# untitled.net
KiCad netlist of a schematic drawn in EAGLE
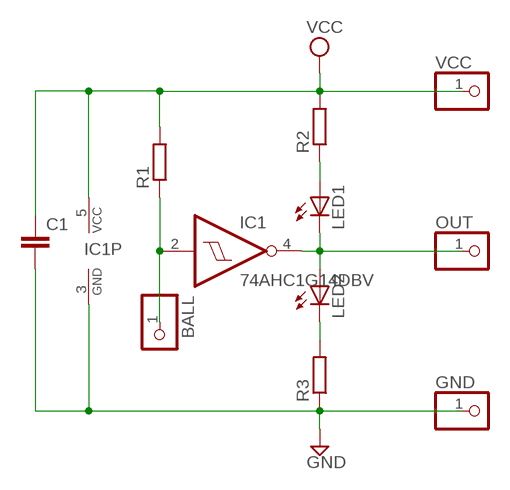
[diagram p0: schematic, sheet 1]

(export (version "E")
  (design (tool "Eeschema 10.0.6"))
  (components
    (comp (ref "BALL")
      (value "PINHD-1X1")
      (footprint "eagle-import:1X01")
      (libsource (lib "eagle-import") (part "PINHD-1X1"))
    )
    (comp (ref "C1")
      (value "C-EUC0805")
      (footprint "eagle-import:C0805")
      (libsource (lib "eagle-import") (part "C-EUC0805"))
    )
    (comp (ref "GND")
      (value "PINHD-1X1")
      (footprint "eagle-import:1X01")
      (libsource (lib "eagle-import") (part "PINHD-1X1"))
    )
    (comp (ref "IC1")
      (value "74AHC1G14DBV")
      (footprint "eagle-import:SOT23-5")
      (libsource (lib "eagle-import") (part "741G14DBVAHC"))
    )
    (comp (ref "LED1")
      (value "LEDCHIP-LED0805")
      (footprint "eagle-import:CHIP-LED0805")
      (libsource (lib "eagle-import") (part "LEDCHIP-LED0805"))
    )
    (comp (ref "LED2")
      (value "LEDCHIP-LED0805")
      (footprint "eagle-import:CHIP-LED0805")
      (libsource (lib "eagle-import") (part "LEDCHIP-LED0805"))
    )
    (comp (ref "OUT")
      (value "PINHD-1X1")
      (footprint "eagle-import:1X01")
      (libsource (lib "eagle-import") (part "PINHD-1X1"))
    )
    (comp (ref "R1")
      (value "R-EU_R0805")
      (footprint "eagle-import:R0805")
      (libsource (lib "eagle-import") (part "R-EU_R0805"))
    )
    (comp (ref "R2")
      (value "R-EU_R0805")
      (footprint "eagle-import:R0805")
      (libsource (lib "eagle-import") (part "R-EU_R0805"))
    )
    (comp (ref "R3")
      (value "R-EU_R0805")
      (footprint "eagle-import:R0805")
      (libsource (lib "eagle-import") (part "R-EU_R0805"))
    )
    (comp (ref "VCC")
      (value "PINHD-1X1")
      (footprint "eagle-import:1X01")
      (libsource (lib "eagle-import") (part "PINHD-1X1"))
    )
  )
  (nets
    (net (code "1") (name "GND") (class "Default")
      (node (ref "C1") (pin "2") (pinfunction "2_2") (pintype "passive"))
      (node (ref "GND") (pin "1") (pinfunction "1_1") (pintype "passive"))
      (node (ref "IC1") (pin "3") (pinfunction "GND_3") (pintype "power_in"))
      (node (ref "R3") (pin "1") (pinfunction "1_1") (pintype "passive"))
    )
    (net (code "2") (name "Net-(IC1A-I)") (class "Default")
      (node (ref "BALL") (pin "1") (pinfunction "1_1") (pintype "passive"))
      (node (ref "IC1") (pin "2") (pinfunction "I_2") (pintype "input"))
      (node (ref "R1") (pin "1") (pinfunction "1_1") (pintype "passive"))
    )
    (net (code "3") (name "Net-(IC1A-O)") (class "Default")
      (node (ref "IC1") (pin "4") (pinfunction "O_4") (pintype "output"))
      (node (ref "LED1") (pin "C") (pinfunction "C_C") (pintype "passive"))
      (node (ref "LED2") (pin "A") (pinfunction "A_A") (pintype "passive"))
      (node (ref "OUT") (pin "1") (pinfunction "1_1") (pintype "passive"))
    )
    (net (code "4") (name "Net-(LED1-PadA)") (class "Default")
      (node (ref "LED1") (pin "A") (pinfunction "A_A") (pintype "passive"))
      (node (ref "R2") (pin "1") (pinfunction "1_1") (pintype "passive"))
    )
    (net (code "5") (name "Net-(LED2-PadC)") (class "Default")
      (node (ref "LED2") (pin "C") (pinfunction "C_C") (pintype "passive"))
      (node (ref "R3") (pin "2") (pinfunction "2_2") (pintype "passive"))
    )
    (net (code "6") (name "VCC") (class "Default")
      (node (ref "C1") (pin "1") (pinfunction "1_1") (pintype "passive"))
      (node (ref "IC1") (pin "5") (pinfunction "VCC_5") (pintype "power_in"))
      (node (ref "R1") (pin "2") (pinfunction "2_2") (pintype "passive"))
      (node (ref "R2") (pin "2") (pinfunction "2_2") (pintype "passive"))
      (node (ref "VCC") (pin "1") (pinfunction "1_1") (pintype "passive"))
    )
  )
)
